# QCopterMV_USB_Sch.net
KiCad netlist of a schematic drawn in Altium Designer
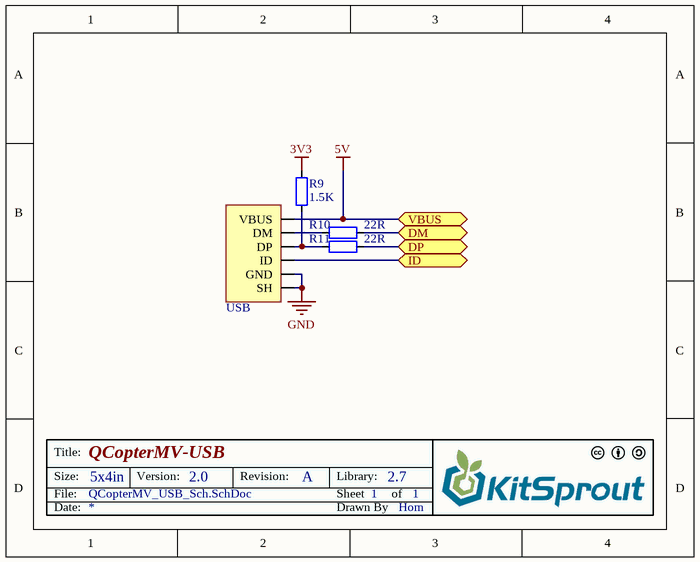
[diagram p0: QCopterMV_USB_Sch.SchDoc]

(export (version "E")
  (design (tool "Eeschema 10.0.6"))
  (components
    (comp (ref "R9")
      (value "1.5K")
      (footprint "PCB_PassiveRes:RES_0402")
      (description "Resistor")
      (fields (field (name "Comment") "Res_0402"))
      (libsource (lib "") (part "Res_0402_1"))
    )
    (comp (ref "R10")
      (value "22R")
      (footprint "PCB_PassiveRes:RES_0402")
      (description "Resistor")
      (fields (field (name "Comment") "Res_0402"))
      (libsource (lib "SCH_Passive") (part "Res_0402"))
    )
    (comp (ref "R11")
      (value "22R")
      (footprint "PCB_PassiveRes:RES_0402")
      (description "Resistor")
      (fields (field (name "Comment") "Res_0402"))
      (libsource (lib "SCH_Passive") (part "Res_0402"))
    )
    (comp (ref "USB")
      (value "USB_Micro")
      (footprint "PCB_USB:USB_Micro-AB")
      (description "USB")
      (libsource (lib "SCH_USB") (part "USB_Micro"))
    )
  )
  (nets
    (net (code "1") (name "/DM") (class "Default")
      (node (ref "R10") (pin "1") (pinfunction "1_1") (pintype "passive"))
    )
    (net (code "2") (name "/DP") (class "Default")
      (node (ref "R11") (pin "1") (pinfunction "1_1") (pintype "passive"))
    )
    (net (code "3") (name "/ID") (class "Default")
      (node (ref "USB") (pin "4") (pinfunction "ID_4") (pintype "passive"))
    )
    (net (code "4") (name "3V3") (class "Default")
      (node (ref "R9") (pin "2") (pinfunction "2_2") (pintype "passive"))
    )
    (net (code "5") (name "5V") (class "Default")
      (node (ref "USB") (pin "1") (pinfunction "VBUS_1") (pintype "passive"))
    )
    (net (code "6") (name "GND") (class "Default")
      (node (ref "USB") (pin "0") (pinfunction "SH_0") (pintype "passive"))
      (node (ref "USB") (pin "5") (pinfunction "GND_5") (pintype "passive"))
    )
    (net (code "7") (name "Net-(USB-DM)") (class "Default")
      (node (ref "R10") (pin "2") (pinfunction "2_2") (pintype "passive"))
      (node (ref "USB") (pin "2") (pinfunction "DM_2") (pintype "passive"))
    )
    (net (code "8") (name "Net-(USB-DP)") (class "Default")
      (node (ref "R11") (pin "2") (pinfunction "2_2") (pintype "passive"))
      (node (ref "R9") (pin "1") (pinfunction "1_1") (pintype "passive"))
      (node (ref "USB") (pin "3") (pinfunction "DP_3") (pintype "passive"))
    )
  )
)
